# RejsaCAN_v3_4_-_Schematic.net
KiCad netlist of a schematic drawn in EasyEDA
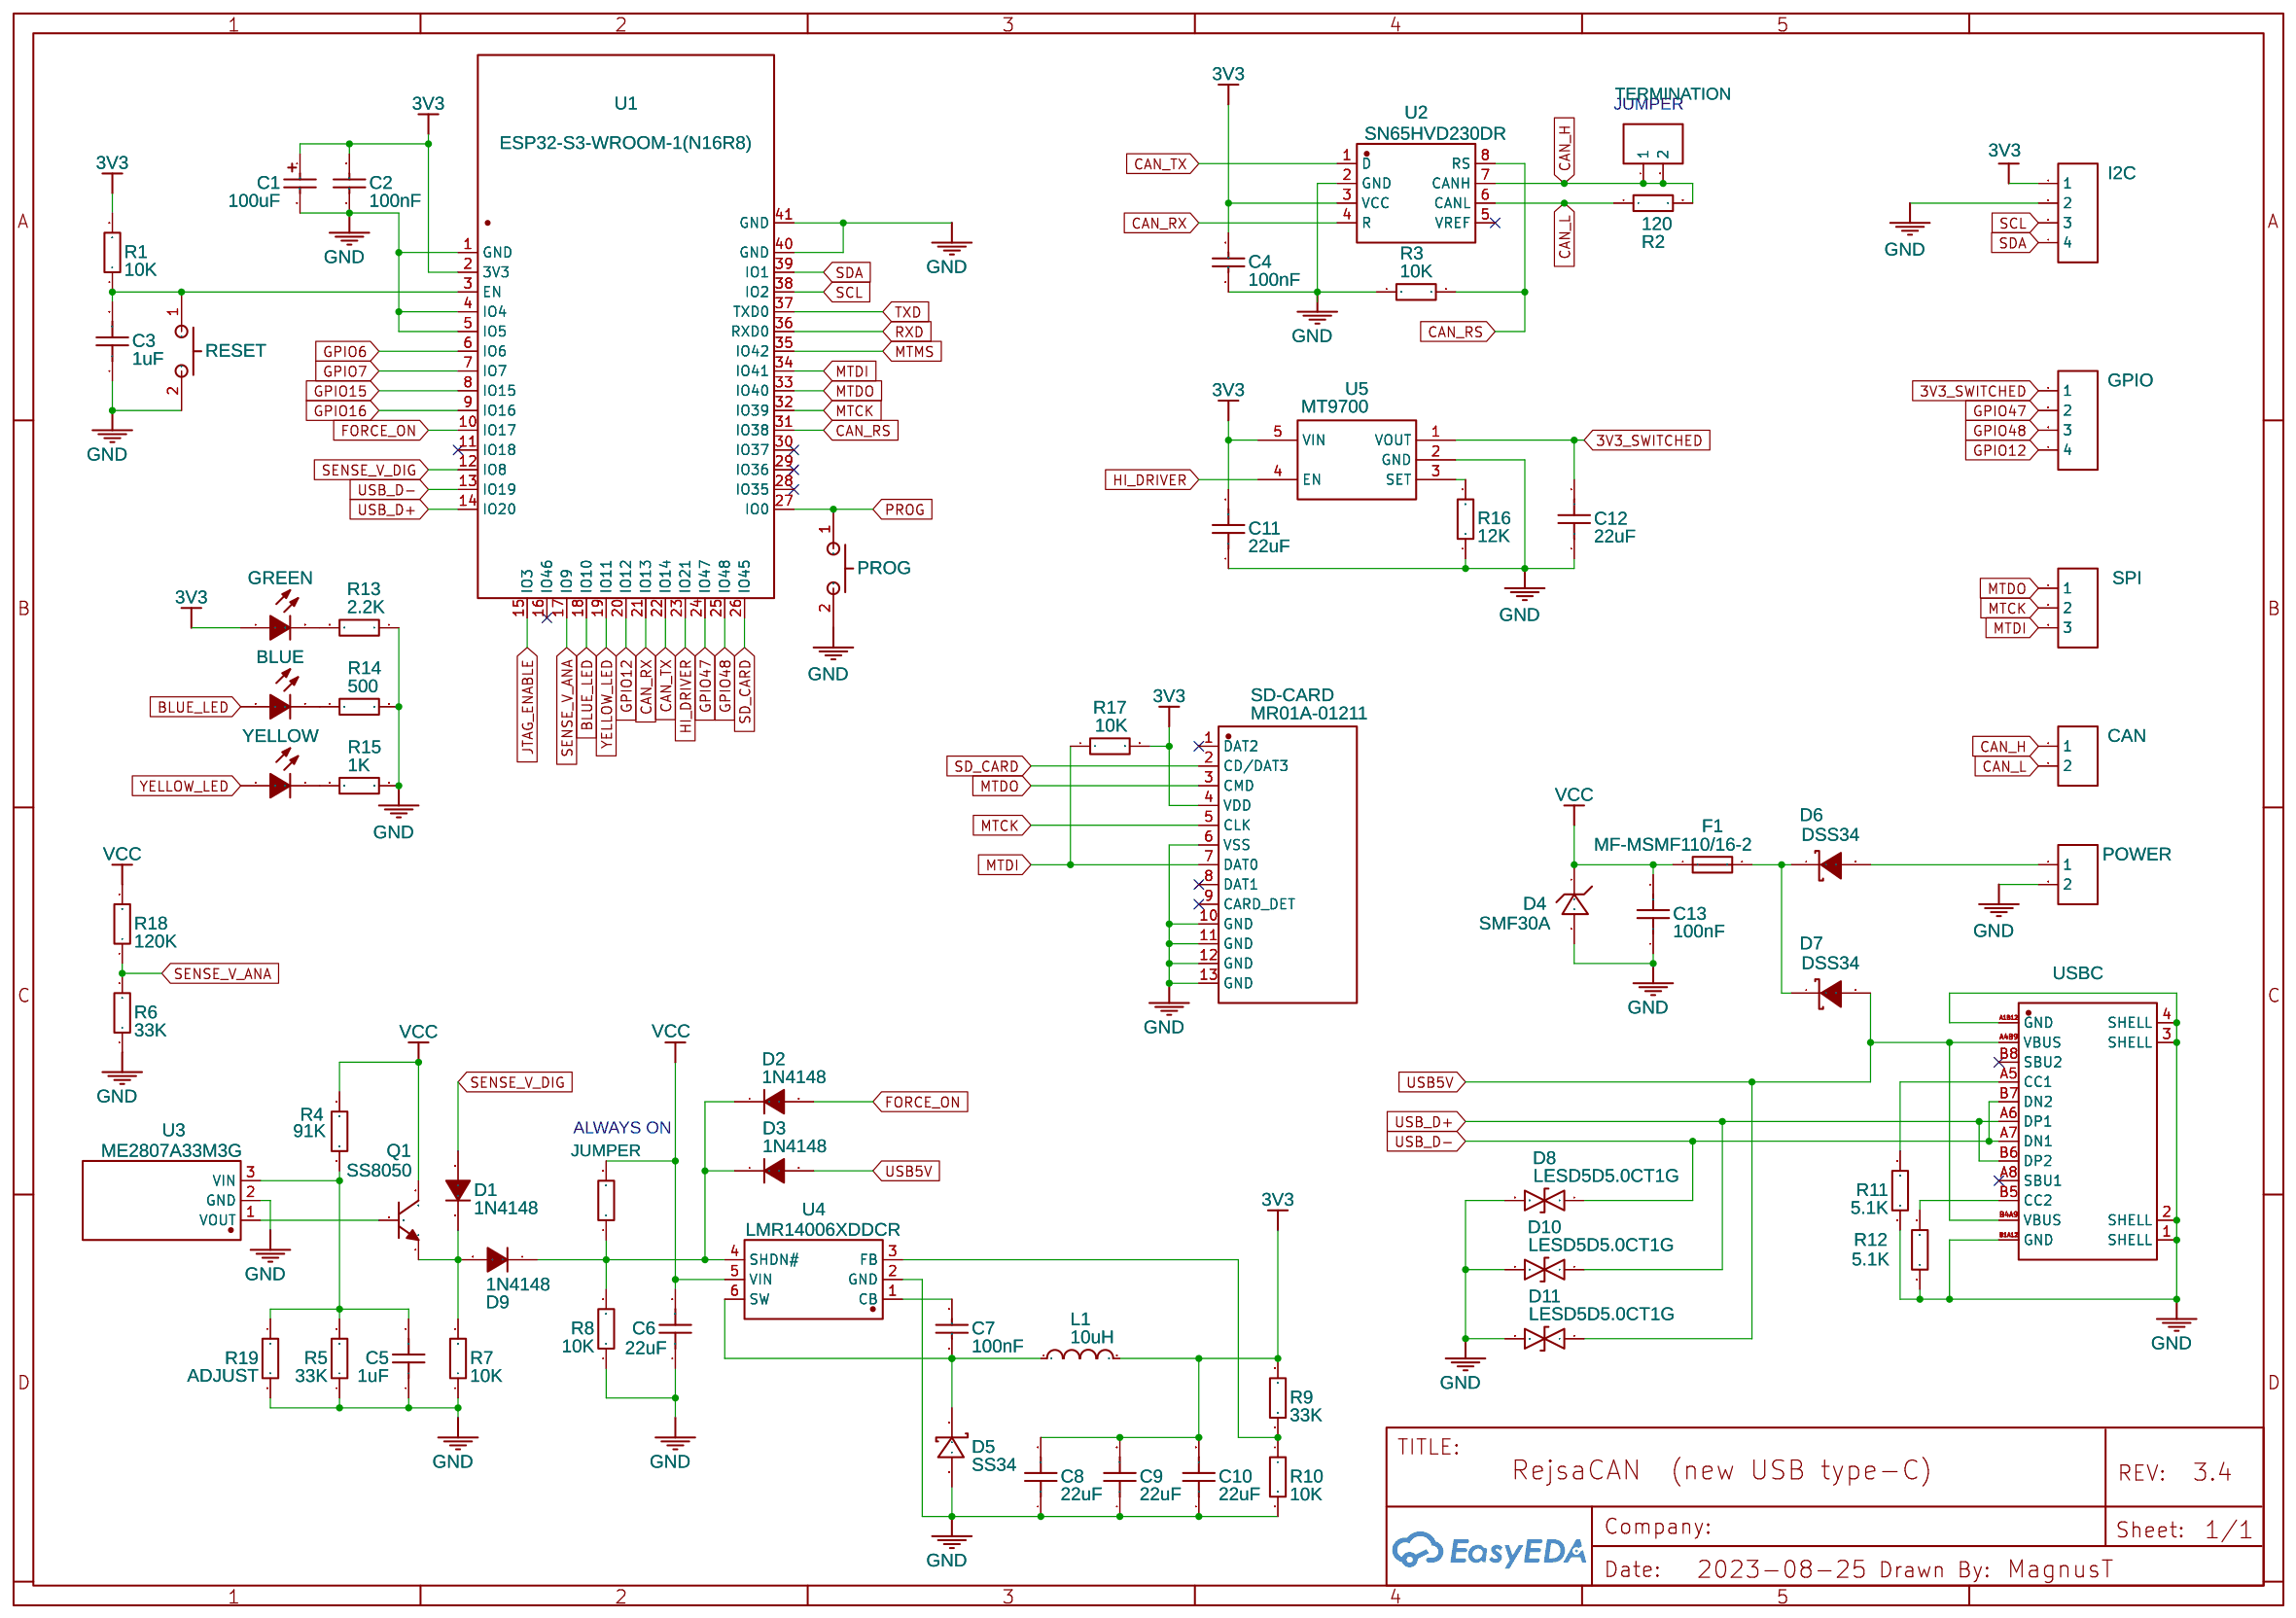
[diagram p0: schematic sheet]

(export (version "E")
  (design (tool "Eeschema 10.0.6"))
  (components
    (comp (ref "BLUE")
      (value "19-217/BHC-ZL1M2RY/3T")
      (fields (field (name "Manufacturer") "EVERLIGHT"))
      (libsource (lib "") (part "19-217/BHC-ZL1M2RY/3T"))
    )
    (comp (ref "C1")
      (value "100uF")
      (fields (field (name "Manufacturer Part") "TAJB107K006RNJ") (field (name "Manufacturer") "AVX"))
      (libsource (lib "") (part "TAJB107K006RNJ"))
    )
    (comp (ref "C2")
      (value "100nF")
      (fields (field (name "Manufacturer Part") "CL05B104KO5NNNC") (field (name "Manufacturer") "SAMSUNG"))
      (libsource (lib "") (part "CL05B104KO5NNNC"))
    )
    (comp (ref "C3")
      (value "1uF")
      (fields (field (name "Manufacturer Part") "CL05A105KA5NQNC") (field (name "Manufacturer") "SAMSUNG"))
      (libsource (lib "") (part "CL05A105KA5NQNC_1"))
    )
    (comp (ref "C4")
      (value "100nF")
      (fields (field (name "Manufacturer Part") "CL05B104KO5NNNC") (field (name "Manufacturer") "SAMSUNG"))
      (libsource (lib "") (part "CL05B104KO5NNNC"))
    )
    (comp (ref "C5")
      (value "1uF")
      (fields (field (name "Manufacturer Part") "CL05A105KA5NQNC") (field (name "Manufacturer") "SAMSUNG"))
      (libsource (lib "") (part "CL05A105KA5NQNC"))
    )
    (comp (ref "C6")
      (value "22uF")
      (fields
        (field (name "Manufacturer Part") "CL21A226MAYNNNE")
        (field (name "Manufacturer") "Samsung Electro-Mechanics")
      )
      (libsource (lib "") (part "CL21A226MAYNNNE"))
    )
    (comp (ref "C7")
      (value "100nF")
      (fields (field (name "Manufacturer Part") "CL05B104KO5NNNC") (field (name "Manufacturer") "SAMSUNG"))
      (libsource (lib "") (part "CL05B104KO5NNNC"))
    )
    (comp (ref "C8")
      (value "22uF")
      (fields (field (name "Manufacturer Part") "CL10A226MQ8NRNC") (field (name "Manufacturer") "SAMSUNG"))
      (libsource (lib "") (part "CL10A226MQ8NRNC"))
    )
    (comp (ref "C9")
      (value "22uF")
      (fields (field (name "Manufacturer Part") "CL10A226MQ8NRNC") (field (name "Manufacturer") "SAMSUNG"))
      (libsource (lib "") (part "CL10A226MQ8NRNC"))
    )
    (comp (ref "C10")
      (value "22uF")
      (fields (field (name "Manufacturer Part") "CL10A226MQ8NRNC") (field (name "Manufacturer") "SAMSUNG"))
      (libsource (lib "") (part "CL10A226MQ8NRNC"))
    )
    (comp (ref "C11")
      (value "22uF")
      (fields (field (name "Manufacturer Part") "CL10A226MQ8NRNC") (field (name "Manufacturer") "SAMSUNG"))
      (libsource (lib "") (part "CL10A226MQ8NRNC"))
    )
    (comp (ref "C12")
      (value "22uF")
      (fields (field (name "Manufacturer Part") "CL10A226MQ8NRNC") (field (name "Manufacturer") "SAMSUNG"))
      (libsource (lib "") (part "CL10A226MQ8NRNC"))
    )
    (comp (ref "C13")
      (value "100nF")
      (fields
        (field (name "Manufacturer Part") "CL05B104KB54PNC")
        (field (name "Manufacturer") "Samsung Electro-Mechanics")
      )
      (libsource (lib "") (part "CL05B104KB54PNC"))
    )
    (comp (ref "CAN") (value "HDR-M-2.54_1x2") (libsource (lib "") (part "HDR-M-2.54_1x2_2")))
    (comp (ref "D1")
      (value "1N4148")
      (fields (field (name "Manufacturer Part") "1N4148WS T4") (field (name "Manufacturer") "CJ"))
      (libsource (lib "") (part "1N4148WS T4"))
    )
    (comp (ref "D2")
      (value "1N4148")
      (fields (field (name "Manufacturer Part") "1N4148WS T4") (field (name "Manufacturer") "CJ"))
      (libsource (lib "") (part "1N4148WS T4_2"))
    )
    (comp (ref "D3")
      (value "1N4148")
      (fields (field (name "Manufacturer Part") "1N4148WS T4") (field (name "Manufacturer") "CJ"))
      (libsource (lib "") (part "1N4148WS T4_2"))
    )
    (comp (ref "D4")
      (value "SMF30A")
      (fields (field (name "Manufacturer") "DOWO"))
      (libsource (lib "") (part "SMF30A_C366558"))
    )
    (comp (ref "D5")
      (value "SS34")
      (fields (field (name "Manufacturer") "MDD"))
      (libsource (lib "") (part "SS34_C8678"))
    )
    (comp (ref "D6")
      (value "DSS34")
      (fields (field (name "Manufacturer") "STARSEA"))
      (libsource (lib "") (part "DSS34"))
    )
    (comp (ref "D7")
      (value "DSS34")
      (fields (field (name "Manufacturer") "STARSEA"))
      (libsource (lib "") (part "DSS34"))
    )
    (comp (ref "D8")
      (value "LESD5D5.0CT1G")
      (fields (field (name "Manufacturer") "Leshan Radio"))
      (libsource (lib "") (part "LESD5D5.0CT1G"))
    )
    (comp (ref "D9")
      (value "1N4148")
      (fields (field (name "Manufacturer Part") "1N4148WS T4") (field (name "Manufacturer") "CJ"))
      (libsource (lib "") (part "1N4148WS T4_1"))
    )
    (comp (ref "D10")
      (value "LESD5D5.0CT1G")
      (fields (field (name "Manufacturer") "Leshan Radio"))
      (libsource (lib "") (part "LESD5D5.0CT1G"))
    )
    (comp (ref "D11")
      (value "LESD5D5.0CT1G")
      (fields (field (name "Manufacturer") "Leshan Radio"))
      (libsource (lib "") (part "LESD5D5.0CT1G"))
    )
    (comp (ref "F1")
      (value "MF-MSMF110/16-2")
      (fields (field (name "Manufacturer") "BOURNS"))
      (libsource (lib "") (part "MF-MSMF110/16-2"))
    )
    (comp (ref "GPIO") (value "HDR-M-2.54_1x4") (libsource (lib "") (part "HDR-M-2.54_1x4_1")))
    (comp (ref "GREEN")
      (value "19-217/GHC-YR1S2/3T")
      (fields (field (name "Manufacturer") "EVERLIGHT"))
      (libsource (lib "") (part "19-217/GHC-YR1S2/3T"))
    )
    (comp (ref "I2C") (value "HDR-M-2.54_1x4") (libsource (lib "") (part "HDR-M-2.54_1x4")))
    (comp (ref "JUMPER") (value "-") (libsource (lib "") (part "0402WGF3092TCE")))
    (comp (ref "L1")
      (value "10uH")
      (fields
        (field (name "Manufacturer Part") "SLP6028S100MTT")
        (field (name "Manufacturer") "Sunltech Tech")
      )
      (libsource (lib "") (part "SLP6028S100MTT"))
    )
    (comp (ref "POWER") (value "HDR-M-2.54_1x2") (libsource (lib "") (part "HDR-M-2.54_1x2_1")))
    (comp (ref "PROG")
      (value "GT-TC029B-H025-L1N")
      (fields (field (name "Manufacturer") "G-Switch"))
      (libsource (lib "") (part "GT-TC029B-H025-L1N_1"))
    )
    (comp (ref "Q1")
      (value "SS8050")
      (fields (field (name "Manufacturer") "CJ"))
      (libsource (lib "") (part "SS8050_C2150"))
    )
    (comp (ref "R1")
      (value "10K")
      (fields (field (name "Manufacturer Part") "0402WGF1002TCE") (field (name "Manufacturer") "UniOhm"))
      (libsource (lib "") (part "0402WGF1002TCE_2"))
    )
    (comp (ref "R2")
      (value "120")
      (fields (field (name "Manufacturer Part") "RTT061200FTP") (field (name "Manufacturer") "RALEC"))
      (libsource (lib "") (part "RTT061200FTP"))
    )
    (comp (ref "R3")
      (value "10K")
      (fields (field (name "Manufacturer Part") "0402WGF1002TCE") (field (name "Manufacturer") "UniOhm"))
      (libsource (lib "") (part "0402WGF1002TCE_1"))
    )
    (comp (ref "R4")
      (value "91K")
      (fields (field (name "Manufacturer Part") "0402WGF9102TCE") (field (name "Manufacturer") "UniOhm"))
      (libsource (lib "") (part "0402WGF9102TCE"))
    )
    (comp (ref "R5")
      (value "33K")
      (fields (field (name "Manufacturer Part") "0402WGF3302TCE") (field (name "Manufacturer") "UniOhm"))
      (libsource (lib "") (part "0402WGF3302TCE"))
    )
    (comp (ref "R6")
      (value "33K")
      (fields (field (name "Manufacturer Part") "0402WGF3302TCE") (field (name "Manufacturer") "UniOhm"))
      (libsource (lib "") (part "0402WGF3302TCE"))
    )
    (comp (ref "R7")
      (value "10K")
      (fields (field (name "Manufacturer Part") "0402WGF1002TCE") (field (name "Manufacturer") "UniOhm"))
      (libsource (lib "") (part "0402WGF1002TCE_2"))
    )
    (comp (ref "R8")
      (value "10K")
      (fields (field (name "Manufacturer Part") "0402WGF1002TCE") (field (name "Manufacturer") "UniOhm"))
      (libsource (lib "") (part "0402WGF1002TCE_2"))
    )
    (comp (ref "R9")
      (value "33K")
      (fields (field (name "Manufacturer Part") "0402WGF3302TCE") (field (name "Manufacturer") "UniOhm"))
      (libsource (lib "") (part "0402WGF3302TCE"))
    )
    (comp (ref "R10")
      (value "10K")
      (fields (field (name "Manufacturer Part") "0402WGF1002TCE") (field (name "Manufacturer") "UniOhm"))
      (libsource (lib "") (part "0402WGF1002TCE"))
    )
    (comp (ref "R11")
      (value "5.1K")
      (fields (field (name "Manufacturer Part") "0402WGF5101TCE") (field (name "Manufacturer") "UniOhm"))
      (libsource (lib "") (part "0402WGF5101TCE"))
    )
    (comp (ref "R12")
      (value "5.1K")
      (fields (field (name "Manufacturer Part") "0402WGF5101TCE") (field (name "Manufacturer") "UniOhm"))
      (libsource (lib "") (part "0402WGF5101TCE"))
    )
    (comp (ref "R13")
      (value "2.2K")
      (fields (field (name "Manufacturer Part") "0402WGF2201TCE") (field (name "Manufacturer") "UniOhm"))
      (libsource (lib "") (part "0402WGF2201TCE"))
    )
    (comp (ref "R14")
      (value "500")
      (fields (field (name "Manufacturer Part") "0402WGF4700TCE") (field (name "Manufacturer") "UniOhm"))
      (libsource (lib "") (part "0402WGF1001TCE"))
    )
    (comp (ref "R15")
      (value "1K")
      (fields (field (name "Manufacturer Part") "0402WGF1001TCE") (field (name "Manufacturer") "UniOhm"))
      (libsource (lib "") (part "0402WGF1001TCE"))
    )
    (comp (ref "R16")
      (value "12K")
      (fields (field (name "Manufacturer Part") "0402WGF1202TCE") (field (name "Manufacturer") "UniOhm"))
      (libsource (lib "") (part "0402WGF1202TCE"))
    )
    (comp (ref "R17")
      (value "10K")
      (fields (field (name "Manufacturer Part") "0402WGF1002TCE") (field (name "Manufacturer") "UniOhm"))
      (libsource (lib "") (part "0402WGF1002TCE_1"))
    )
    (comp (ref "R18")
      (value "120K")
      (fields (field (name "Manufacturer Part") "0402WGF1203TCE") (field (name "Manufacturer") "UniOhm"))
      (libsource (lib "") (part "0402WGF1203TCE"))
    )
    (comp (ref "R19")
      (value "ADJUST")
      (fields (field (name "Manufacturer Part") "0402WGF9102TCE") (field (name "Manufacturer") "UniOhm"))
      (libsource (lib "") (part "0402WGF9102TCE_1"))
    )
    (comp (ref "RESET")
      (value "GT-TC029B-H025-L1N")
      (fields (field (name "Manufacturer") "G-Switch"))
      (libsource (lib "") (part "GT-TC029B-H025-L1N"))
    )
    (comp (ref "SD-CARD")
      (value "MR01A-01211")
      (fields (field (name "Manufacturer") "ATOM(爱特姆)"))
      (libsource (lib "") (part "MR01A-01211"))
    )
    (comp (ref "SPI") (value "HDR-M-2.54_1x3") (libsource (lib "") (part "HDR-M-2.54_1x3")))
    (comp (ref "TERMINATION") (value "HDR-M-2.54_1x2") (libsource (lib "") (part "HDR-M-2.54_1x2")))
    (comp (ref "U1")
      (value "ESP32-S3-WROOM-1(N16R8)")
      (fields (field (name "Manufacturer") "ESPRESSIF(乐鑫)"))
      (libsource (lib "") (part "ESP32-S3-WROOM-1(N16R8)"))
    )
    (comp (ref "U2")
      (value "SN65HVD230DR")
      (fields (field (name "Manufacturer") "TI"))
      (libsource (lib "") (part "SN65HVD230DR"))
    )
    (comp (ref "U3")
      (value "ME2807A33M3G")
      (fields (field (name "Manufacturer") "Nanjing Micro One Elec"))
      (libsource (lib "") (part "ME2807A33M3G"))
    )
    (comp (ref "U4")
      (value "LMR14006XDDCR")
      (fields (field (name "Manufacturer") "Texas Instruments"))
      (libsource (lib "") (part "LMR14006XDDCR"))
    )
    (comp (ref "U5")
      (value "MT9700")
      (fields (field (name "Manufacturer") "AEROSEMI"))
      (libsource (lib "") (part "MT9700"))
    )
    (comp (ref "USBC")
      (value "GT-USB-7010ASV")
      (fields (field (name "Manufacturer") "G-Switch(品赞)"))
      (libsource (lib "") (part "GT-USB-7010ASV"))
    )
    (comp (ref "YELLOW")
      (value "19-213/Y2C-CQ2R2L/3T(CY)")
      (fields (field (name "Manufacturer") "EVERLIGHT"))
      (libsource (lib "") (part "19-213/Y2C-CQ2R2L/3T(CY)"))
    )
  )
  (nets
    (net (code "1") (name "3V3") (class "Default")
      (node (ref "C1") (pin "1") (pinfunction "1_1") (pintype "input"))
      (node (ref "C10") (pin "2") (pinfunction "2_2") (pintype "unspecified"))
      (node (ref "C11") (pin "2") (pinfunction "2_2") (pintype "unspecified"))
      (node (ref "C2") (pin "2") (pinfunction "2_2") (pintype "input"))
      (node (ref "C4") (pin "2") (pinfunction "2_2") (pintype "input"))
      (node (ref "C8") (pin "2") (pinfunction "2_2") (pintype "unspecified"))
      (node (ref "C9") (pin "2") (pinfunction "2_2") (pintype "unspecified"))
      (node (ref "GREEN") (pin "1") (pinfunction "A_1") (pintype "input"))
      (node (ref "I2C") (pin "1") (pinfunction "1_1") (pintype "unspecified"))
      (node (ref "L1") (pin "2") (pinfunction "2_2") (pintype "unspecified"))
      (node (ref "R1") (pin "2") (pinfunction "2_2") (pintype "input"))
      (node (ref "R17") (pin "2") (pinfunction "2_2") (pintype "input"))
      (node (ref "R9") (pin "2") (pinfunction "2_2") (pintype "input"))
      (node (ref "SD-CARD") (pin "4") (pinfunction "VDD_4") (pintype "unspecified"))
      (node (ref "U1") (pin "2") (pinfunction "3V3_2") (pintype "unspecified"))
      (node (ref "U2") (pin "3") (pinfunction "VCC_3") (pintype "unspecified"))
      (node (ref "U5") (pin "5") (pinfunction "VIN_5") (pintype "unspecified"))
    )
    (net (code "2") (name "3V3_SWITCHED") (class "Default")
      (node (ref "C12") (pin "2") (pinfunction "2_2") (pintype "unspecified"))
      (node (ref "GPIO") (pin "1") (pinfunction "1_1") (pintype "unspecified"))
      (node (ref "U5") (pin "1") (pinfunction "VOUT_1") (pintype "unspecified"))
    )
    (net (code "3") (name "BLUE_LED") (class "Default")
      (node (ref "BLUE") (pin "1") (pinfunction "A_1") (pintype "input"))
      (node (ref "U1") (pin "18") (pinfunction "IO10_18") (pintype "unspecified"))
    )
    (net (code "4") (name "CAN_H") (class "Default")
      (node (ref "CAN") (pin "1") (pinfunction "1_1") (pintype "unspecified"))
      (node (ref "R2") (pin "2") (pinfunction "2_2") (pintype "unspecified"))
      (node (ref "TERMINATION") (pin "1") (pinfunction "1_1") (pintype "unspecified"))
      (node (ref "TERMINATION") (pin "2") (pinfunction "2_2") (pintype "unspecified"))
      (node (ref "U2") (pin "7") (pinfunction "CANH_7") (pintype "unspecified"))
    )
    (net (code "5") (name "CAN_L") (class "Default")
      (node (ref "CAN") (pin "2") (pinfunction "2_2") (pintype "unspecified"))
      (node (ref "R2") (pin "1") (pinfunction "1_1") (pintype "unspecified"))
      (node (ref "U2") (pin "6") (pinfunction "CANL_6") (pintype "unspecified"))
    )
    (net (code "6") (name "CAN_RS") (class "Default")
      (node (ref "R3") (pin "2") (pinfunction "2_2") (pintype "input"))
      (node (ref "U1") (pin "31") (pinfunction "IO38_31") (pintype "unspecified"))
      (node (ref "U2") (pin "8") (pinfunction "RS_8") (pintype "unspecified"))
    )
    (net (code "7") (name "CAN_RX") (class "Default")
      (node (ref "U1") (pin "21") (pinfunction "IO13_21") (pintype "unspecified"))
      (node (ref "U2") (pin "4") (pinfunction "R_4") (pintype "unspecified"))
    )
    (net (code "8") (name "CAN_TX") (class "Default")
      (node (ref "U1") (pin "22") (pinfunction "IO14_22") (pintype "unspecified"))
      (node (ref "U2") (pin "1") (pinfunction "D_1") (pintype "unspecified"))
    )
    (net (code "9") (name "FORCE_ON") (class "Default")
      (node (ref "D2") (pin "2") (pinfunction "A_2") (pintype "unspecified"))
      (node (ref "U1") (pin "10") (pinfunction "IO17_10") (pintype "unspecified"))
    )
    (net (code "10") (name "GND") (class "Default")
      (node (ref "C1") (pin "2") (pinfunction "2_2") (pintype "input"))
      (node (ref "C10") (pin "1") (pinfunction "1_1") (pintype "unspecified"))
      (node (ref "C11") (pin "1") (pinfunction "1_1") (pintype "unspecified"))
      (node (ref "C12") (pin "1") (pinfunction "1_1") (pintype "unspecified"))
      (node (ref "C13") (pin "1") (pinfunction "1_1") (pintype "unspecified"))
      (node (ref "C2") (pin "1") (pinfunction "1_1") (pintype "input"))
      (node (ref "C3") (pin "1") (pinfunction "1_1") (pintype "unspecified"))
      (node (ref "C4") (pin "1") (pinfunction "1_1") (pintype "input"))
      (node (ref "C5") (pin "1") (pinfunction "1_1") (pintype "unspecified"))
      (node (ref "C6") (pin "1") (pinfunction "1_1") (pintype "unspecified"))
      (node (ref "C8") (pin "1") (pinfunction "1_1") (pintype "unspecified"))
      (node (ref "C9") (pin "1") (pinfunction "1_1") (pintype "unspecified"))
      (node (ref "D10") (pin "2") (pinfunction "2_2") (pintype "unspecified"))
      (node (ref "D11") (pin "2") (pinfunction "2_2") (pintype "unspecified"))
      (node (ref "D4") (pin "2") (pinfunction "2_2") (pintype "unspecified"))
      (node (ref "D5") (pin "2") (pinfunction "A_2") (pintype "unspecified"))
      (node (ref "D8") (pin "2") (pinfunction "2_2") (pintype "unspecified"))
      (node (ref "I2C") (pin "2") (pinfunction "2_2") (pintype "unspecified"))
      (node (ref "POWER") (pin "2") (pinfunction "2_2") (pintype "unspecified"))
      (node (ref "PROG") (pin "2") (pinfunction "2_2") (pintype "unspecified"))
      (node (ref "R10") (pin "2") (pinfunction "2_2") (pintype "input"))
      (node (ref "R11") (pin "1") (pinfunction "1_1") (pintype "input"))
      (node (ref "R12") (pin "1") (pinfunction "1_1") (pintype "input"))
      (node (ref "R13") (pin "1") (pinfunction "1_1") (pintype "input"))
      (node (ref "R14") (pin "2") (pinfunction "2_2") (pintype "input"))
      (node (ref "R15") (pin "2") (pinfunction "2_2") (pintype "input"))
      (node (ref "R16") (pin "1") (pinfunction "1_1") (pintype "input"))
      (node (ref "R19") (pin "2") (pinfunction "2_2") (pintype "input"))
      (node (ref "R3") (pin "1") (pinfunction "1_1") (pintype "input"))
      (node (ref "R5") (pin "1") (pinfunction "1_1") (pintype "input"))
      (node (ref "R6") (pin "1") (pinfunction "1_1") (pintype "input"))
      (node (ref "R7") (pin "1") (pinfunction "1_1") (pintype "input"))
      (node (ref "R8") (pin "1") (pinfunction "1_1") (pintype "input"))
      (node (ref "RESET") (pin "2") (pinfunction "2_2") (pintype "unspecified"))
      (node (ref "SD-CARD") (pin "10") (pinfunction "GND_10") (pintype "unspecified"))
      (node (ref "SD-CARD") (pin "11") (pinfunction "GND_11") (pintype "unspecified"))
      (node (ref "SD-CARD") (pin "12") (pinfunction "GND_12") (pintype "unspecified"))
      (node (ref "SD-CARD") (pin "13") (pinfunction "GND_13") (pintype "unspecified"))
      (node (ref "SD-CARD") (pin "6") (pinfunction "VSS_6") (pintype "unspecified"))
      (node (ref "U1") (pin "1") (pinfunction "GND_1") (pintype "unspecified"))
      (node (ref "U1") (pin "4") (pinfunction "IO4_4") (pintype "unspecified"))
      (node (ref "U1") (pin "40") (pinfunction "GND_40") (pintype "unspecified"))
      (node (ref "U1") (pin "41") (pinfunction "GND_41") (pintype "unspecified"))
      (node (ref "U1") (pin "5") (pinfunction "IO5_5") (pintype "unspecified"))
      (node (ref "U2") (pin "2") (pinfunction "GND_2") (pintype "unspecified"))
      (node (ref "U3") (pin "2") (pinfunction "GND_2") (pintype "unspecified"))
      (node (ref "U4") (pin "2") (pinfunction "GND_2") (pintype "unspecified"))
      (node (ref "U5") (pin "2") (pinfunction "GND_2") (pintype "unspecified"))
      (node (ref "USBC") (pin "1") (pinfunction "SHELL_1") (pintype "unspecified"))
      (node (ref "USBC") (pin "2") (pinfunction "SHELL_2") (pintype "unspecified"))
      (node (ref "USBC") (pin "3") (pinfunction "SHELL_3") (pintype "unspecified"))
      (node (ref "USBC") (pin "4") (pinfunction "SHELL_4") (pintype "unspecified"))
      (node (ref "USBC") (pin "A1B12") (pinfunction "GND_A1B12") (pintype "unspecified"))
      (node (ref "USBC") (pin "B1A12") (pinfunction "GND_B1A12") (pintype "unspecified"))
    )
    (net (code "11") (name "GPIO6") (class "Default")
      (node (ref "U1") (pin "6") (pinfunction "IO6_6") (pintype "unspecified"))
    )
    (net (code "12") (name "GPIO7") (class "Default")
      (node (ref "U1") (pin "7") (pinfunction "IO7_7") (pintype "unspecified"))
    )
    (net (code "13") (name "GPIO12") (class "Default")
      (node (ref "GPIO") (pin "4") (pinfunction "4_4") (pintype "unspecified"))
      (node (ref "U1") (pin "20") (pinfunction "IO12_20") (pintype "unspecified"))
    )
    (net (code "14") (name "GPIO15") (class "Default")
      (node (ref "U1") (pin "8") (pinfunction "IO15_8") (pintype "unspecified"))
    )
    (net (code "15") (name "GPIO16") (class "Default")
      (node (ref "U1") (pin "9") (pinfunction "IO16_9") (pintype "unspecified"))
    )
    (net (code "16") (name "GPIO47") (class "Default")
      (node (ref "GPIO") (pin "2") (pinfunction "2_2") (pintype "unspecified"))
      (node (ref "U1") (pin "24") (pinfunction "IO47_24") (pintype "unspecified"))
    )
    (net (code "17") (name "GPIO48") (class "Default")
      (node (ref "GPIO") (pin "3") (pinfunction "3_3") (pintype "unspecified"))
      (node (ref "U1") (pin "25") (pinfunction "IO48_25") (pintype "unspecified"))
    )
    (net (code "18") (name "HI_DRIVER") (class "Default")
      (node (ref "U1") (pin "23") (pinfunction "IO21_23") (pintype "unspecified"))
      (node (ref "U5") (pin "4") (pinfunction "EN_4") (pintype "unspecified"))
    )
    (net (code "19") (name "JTAG_ENABLE") (class "Default")
      (node (ref "U1") (pin "15") (pinfunction "IO3_15") (pintype "unspecified"))
    )
    (net (code "20") (name "MTCK") (class "Default")
      (node (ref "SD-CARD") (pin "5") (pinfunction "CLK_5") (pintype "unspecified"))
      (node (ref "SPI") (pin "2") (pinfunction "2_2") (pintype "input"))
      (node (ref "U1") (pin "32") (pinfunction "IO39_32") (pintype "unspecified"))
    )
    (net (code "21") (name "MTDI") (class "Default")
      (node (ref "R17") (pin "1") (pinfunction "1_1") (pintype "input"))
      (node (ref "SD-CARD") (pin "7") (pinfunction "DAT0_7") (pintype "unspecified"))
      (node (ref "SPI") (pin "3") (pinfunction "3_3") (pintype "input"))
      (node (ref "U1") (pin "34") (pinfunction "IO41_34") (pintype "unspecified"))
    )
    (net (code "22") (name "MTDO") (class "Default")
      (node (ref "SD-CARD") (pin "3") (pinfunction "CMD_3") (pintype "unspecified"))
      (node (ref "SPI") (pin "1") (pinfunction "1_1") (pintype "input"))
      (node (ref "U1") (pin "33") (pinfunction "IO40_33") (pintype "unspecified"))
    )
    (net (code "23") (name "MTMS") (class "Default")
      (node (ref "U1") (pin "35") (pinfunction "IO42_35") (pintype "unspecified"))
    )
    (net (code "24") (name "Net-(BLUE-C)") (class "Default")
      (node (ref "BLUE") (pin "2") (pinfunction "C_2") (pintype "input"))
      (node (ref "R14") (pin "1") (pinfunction "1_1") (pintype "input"))
    )
    (net (code "25") (name "Net-(D1-K)") (class "Default")
      (node (ref "D1") (pin "1") (pinfunction "K_1") (pintype "unspecified"))
      (node (ref "D9") (pin "2") (pinfunction "A_2") (pintype "unspecified"))
      (node (ref "Q1") (pin "2") (pinfunction "E_2") (pintype "unspecified"))
      (node (ref "R7") (pin "2") (pinfunction "2_2") (pintype "input"))
    )
    (net (code "26") (name "Net-(D2-K)") (class "Default")
      (node (ref "D2") (pin "1") (pinfunction "K_1") (pintype "unspecified"))
      (node (ref "D3") (pin "1") (pinfunction "K_1") (pintype "unspecified"))
      (node (ref "D9") (pin "1") (pinfunction "K_1") (pintype "unspecified"))
      (node (ref "JUMPER") (pin "1") (pinfunction "1_1") (pintype "unspecified"))
      (node (ref "R8") (pin "2") (pinfunction "2_2") (pintype "input"))
      (node (ref "U4") (pin "4") (pinfunction "SHDN#_4") (pintype "unspecified"))
    )
    (net (code "27") (name "Net-(D5-K)") (class "Default")
      (node (ref "C7") (pin "1") (pinfunction "1_1") (pintype "input"))
      (node (ref "D5") (pin "1") (pinfunction "K_1") (pintype "unspecified"))
      (node (ref "L1") (pin "1") (pinfunction "1_1") (pintype "unspecified"))
      (node (ref "U4") (pin "6") (pinfunction "SW_6") (pintype "unspecified"))
    )
    (net (code "28") (name "Net-(D6-A)") (class "Default")
      (node (ref "D6") (pin "2") (pinfunction "A_2") (pintype "unspecified"))
      (node (ref "POWER") (pin "1") (pinfunction "1_1") (pintype "unspecified"))
    )
    (net (code "29") (name "Net-(D6-K)") (class "Default")
      (node (ref "D6") (pin "1") (pinfunction "K_1") (pintype "unspecified"))
      (node (ref "D7") (pin "1") (pinfunction "K_1") (pintype "unspecified"))
      (node (ref "F1") (pin "2") (pinfunction "2_2") (pintype "unspecified"))
    )
    (net (code "30") (name "Net-(GREEN-C)") (class "Default")
      (node (ref "GREEN") (pin "2") (pinfunction "C_2") (pintype "input"))
      (node (ref "R13") (pin "2") (pinfunction "2_2") (pintype "input"))
    )
    (net (code "31") (name "Net-(Q1-B)") (class "Default")
      (node (ref "Q1") (pin "1") (pinfunction "B_1") (pintype "unspecified"))
      (node (ref "U3") (pin "1") (pinfunction "VOUT_1") (pintype "unspecified"))
    )
    (net (code "32") (name "Net-(U1-EN)") (class "Default")
      (node (ref "C3") (pin "2") (pinfunction "2_2") (pintype "unspecified"))
      (node (ref "R1") (pin "1") (pinfunction "1_1") (pintype "input"))
      (node (ref "RESET") (pin "1") (pinfunction "1_1") (pintype "unspecified"))
      (node (ref "U1") (pin "3") (pinfunction "EN_3") (pintype "unspecified"))
    )
    (net (code "33") (name "Net-(U3-VIN)") (class "Default")
      (node (ref "C5") (pin "2") (pinfunction "2_2") (pintype "unspecified"))
      (node (ref "R19") (pin "1") (pinfunction "1_1") (pintype "input"))
      (node (ref "R4") (pin "1") (pinfunction "1_1") (pintype "input"))
      (node (ref "R5") (pin "2") (pinfunction "2_2") (pintype "input"))
      (node (ref "U3") (pin "3") (pinfunction "VIN_3") (pintype "unspecified"))
    )
    (net (code "34") (name "Net-(U4-CB)") (class "Default")
      (node (ref "C7") (pin "2") (pinfunction "2_2") (pintype "input"))
      (node (ref "U4") (pin "1") (pinfunction "CB_1") (pintype "unspecified"))
    )
    (net (code "35") (name "Net-(U4-FB)") (class "Default")
      (node (ref "R10") (pin "1") (pinfunction "1_1") (pintype "input"))
      (node (ref "R9") (pin "1") (pinfunction "1_1") (pintype "input"))
      (node (ref "U4") (pin "3") (pinfunction "FB_3") (pintype "unspecified"))
    )
    (net (code "36") (name "Net-(U5-SET)") (class "Default")
      (node (ref "R16") (pin "2") (pinfunction "2_2") (pintype "input"))
      (node (ref "U5") (pin "3") (pinfunction "SET_3") (pintype "unspecified"))
    )
    (net (code "37") (name "Net-(USBC-CC1)") (class "Default")
      (node (ref "R11") (pin "2") (pinfunction "2_2") (pintype "input"))
      (node (ref "USBC") (pin "A5") (pinfunction "CC1_A5") (pintype "unspecified"))
    )
    (net (code "38") (name "Net-(USBC-CC2)") (class "Default")
      (node (ref "R12") (pin "2") (pinfunction "2_2") (pintype "input"))
      (node (ref "USBC") (pin "B5") (pinfunction "CC2_B5") (pintype "unspecified"))
    )
    (net (code "39") (name "Net-(YELLOW-C)") (class "Default")
      (node (ref "R15") (pin "1") (pinfunction "1_1") (pintype "input"))
      (node (ref "YELLOW") (pin "2") (pinfunction "C_2") (pintype "input"))
    )
    (net (code "40") (name "PROG") (class "Default")
      (node (ref "PROG") (pin "1") (pinfunction "1_1") (pintype "unspecified"))
      (node (ref "U1") (pin "27") (pinfunction "IO0_27") (pintype "unspecified"))
    )
    (net (code "41") (name "RXD") (class "Default")
      (node (ref "U1") (pin "36") (pinfunction "RXD0_36") (pintype "unspecified"))
    )
    (net (code "42") (name "SCL") (class "Default")
      (node (ref "I2C") (pin "3") (pinfunction "3_3") (pintype "unspecified"))
      (node (ref "U1") (pin "38") (pinfunction "IO2_38") (pintype "unspecified"))
    )
    (net (code "43") (name "SDA") (class "Default")
      (node (ref "I2C") (pin "4") (pinfunction "4_4") (pintype "unspecified"))
      (node (ref "U1") (pin "39") (pinfunction "IO1_39") (pintype "unspecified"))
    )
    (net (code "44") (name "SD_CARD") (class "Default")
      (node (ref "SD-CARD") (pin "2") (pinfunction "CD/DAT3_2") (pintype "unspecified"))
      (node (ref "U1") (pin "26") (pinfunction "IO45_26") (pintype "unspecified"))
    )
    (net (code "45") (name "SENSE_V_ANA") (class "Default")
      (node (ref "R18") (pin "1") (pinfunction "1_1") (pintype "input"))
      (node (ref "R6") (pin "2") (pinfunction "2_2") (pintype "input"))
      (node (ref "U1") (pin "17") (pinfunction "IO9_17") (pintype "unspecified"))
    )
    (net (code "46") (name "SENSE_V_DIG") (class "Default")
      (node (ref "D1") (pin "2") (pinfunction "A_2") (pintype "unspecified"))
      (node (ref "U1") (pin "12") (pinfunction "IO8_12") (pintype "unspecified"))
    )
    (net (code "47") (name "TXD") (class "Default")
      (node (ref "U1") (pin "37") (pinfunction "TXD0_37") (pintype "unspecified"))
    )
    (net (code "48") (name "USB5V") (class "Default")
      (node (ref "D11") (pin "1") (pinfunction "1_1") (pintype "unspecified"))
      (node (ref "D3") (pin "2") (pinfunction "A_2") (pintype "unspecified"))
      (node (ref "D7") (pin "2") (pinfunction "A_2") (pintype "unspecified"))
      (node (ref "USBC") (pin "A4B9") (pinfunction "VBUS_A4B9") (pintype "unspecified"))
      (node (ref "USBC") (pin "B4A9") (pinfunction "VBUS_B4A9") (pintype "unspecified"))
    )
    (net (code "49") (name "USB_D+") (class "Default")
      (node (ref "D10") (pin "1") (pinfunction "1_1") (pintype "unspecified"))
      (node (ref "U1") (pin "14") (pinfunction "IO20_14") (pintype "unspecified"))
      (node (ref "USBC") (pin "A6") (pinfunction "DP1_A6") (pintype "unspecified"))
      (node (ref "USBC") (pin "B6") (pinfunction "DP2_B6") (pintype "unspecified"))
    )
    (net (code "50") (name "USB_D-") (class "Default")
      (node (ref "D8") (pin "1") (pinfunction "1_1") (pintype "unspecified"))
      (node (ref "U1") (pin "13") (pinfunction "IO19_13") (pintype "unspecified"))
      (node (ref "USBC") (pin "A7") (pinfunction "DN1_A7") (pintype "unspecified"))
      (node (ref "USBC") (pin "B7") (pinfunction "DN2_B7") (pintype "unspecified"))
    )
    (net (code "51") (name "VCC") (class "Default")
      (node (ref "C13") (pin "2") (pinfunction "2_2") (pintype "unspecified"))
      (node (ref "C6") (pin "2") (pinfunction "2_2") (pintype "unspecified"))
      (node (ref "D4") (pin "1") (pinfunction "1_1") (pintype "unspecified"))
      (node (ref "F1") (pin "1") (pinfunction "1_1") (pintype "unspecified"))
      (node (ref "JUMPER") (pin "2") (pinfunction "2_2") (pintype "unspecified"))
      (node (ref "Q1") (pin "3") (pinfunction "C_3") (pintype "unspecified"))
      (node (ref "R18") (pin "2") (pinfunction "2_2") (pintype "input"))
      (node (ref "R4") (pin "2") (pinfunction "2_2") (pintype "input"))
      (node (ref "U4") (pin "5") (pinfunction "VIN_5") (pintype "unspecified"))
    )
    (net (code "52") (name "YELLOW_LED") (class "Default")
      (node (ref "U1") (pin "19") (pinfunction "IO11_19") (pintype "unspecified"))
      (node (ref "YELLOW") (pin "1") (pinfunction "A_1") (pintype "input"))
    )
    (net (code "53") (name "unconnected-(SD-CARD-CARD_DET-Pad9)") (class "Default")
      (node (ref "SD-CARD") (pin "9") (pinfunction "CARD_DET_9") (pintype "unspecified+no_connect"))
    )
    (net (code "54") (name "unconnected-(SD-CARD-DAT1-Pad8)") (class "Default")
      (node (ref "SD-CARD") (pin "8") (pinfunction "DAT1_8") (pintype "unspecified+no_connect"))
    )
    (net (code "55") (name "unconnected-(SD-CARD-DAT2-Pad1)") (class "Default")
      (node (ref "SD-CARD") (pin "1") (pinfunction "DAT2_1") (pintype "unspecified+no_connect"))
    )
    (net (code "56") (name "unconnected-(U1-IO18-Pad11)") (class "Default")
      (node (ref "U1") (pin "11") (pinfunction "IO18_11") (pintype "unspecified+no_connect"))
    )
    (net (code "57") (name "unconnected-(U1-IO35-Pad28)") (class "Default")
      (node (ref "U1") (pin "28") (pinfunction "IO35_28") (pintype "unspecified+no_connect"))
    )
    (net (code "58") (name "unconnected-(U1-IO36-Pad29)") (class "Default")
      (node (ref "U1") (pin "29") (pinfunction "IO36_29") (pintype "unspecified+no_connect"))
    )
    (net (code "59") (name "unconnected-(U1-IO37-Pad30)") (class "Default")
      (node (ref "U1") (pin "30") (pinfunction "IO37_30") (pintype "unspecified+no_connect"))
    )
    (net (code "60") (name "unconnected-(U1-IO46-Pad16)") (class "Default")
      (node (ref "U1") (pin "16") (pinfunction "IO46_16") (pintype "unspecified+no_connect"))
    )
    (net (code "61") (name "unconnected-(U2-VREF-Pad5)") (class "Default")
      (node (ref "U2") (pin "5") (pinfunction "VREF_5") (pintype "unspecified+no_connect"))
    )
    (net (code "62") (name "unconnected-(USBC-SBU1-PadA8)") (class "Default")
      (node (ref "USBC") (pin "A8") (pinfunction "SBU1_A8") (pintype "unspecified+no_connect"))
    )
    (net (code "63") (name "unconnected-(USBC-SBU2-PadB8)") (class "Default")
      (node (ref "USBC") (pin "B8") (pinfunction "SBU2_B8") (pintype "unspecified+no_connect"))
    )
  )
)
